# ALLPRINT-CAPBOARD-677512-GENERAL.net
KiCad netlist of a schematic drawn in Altium Designer
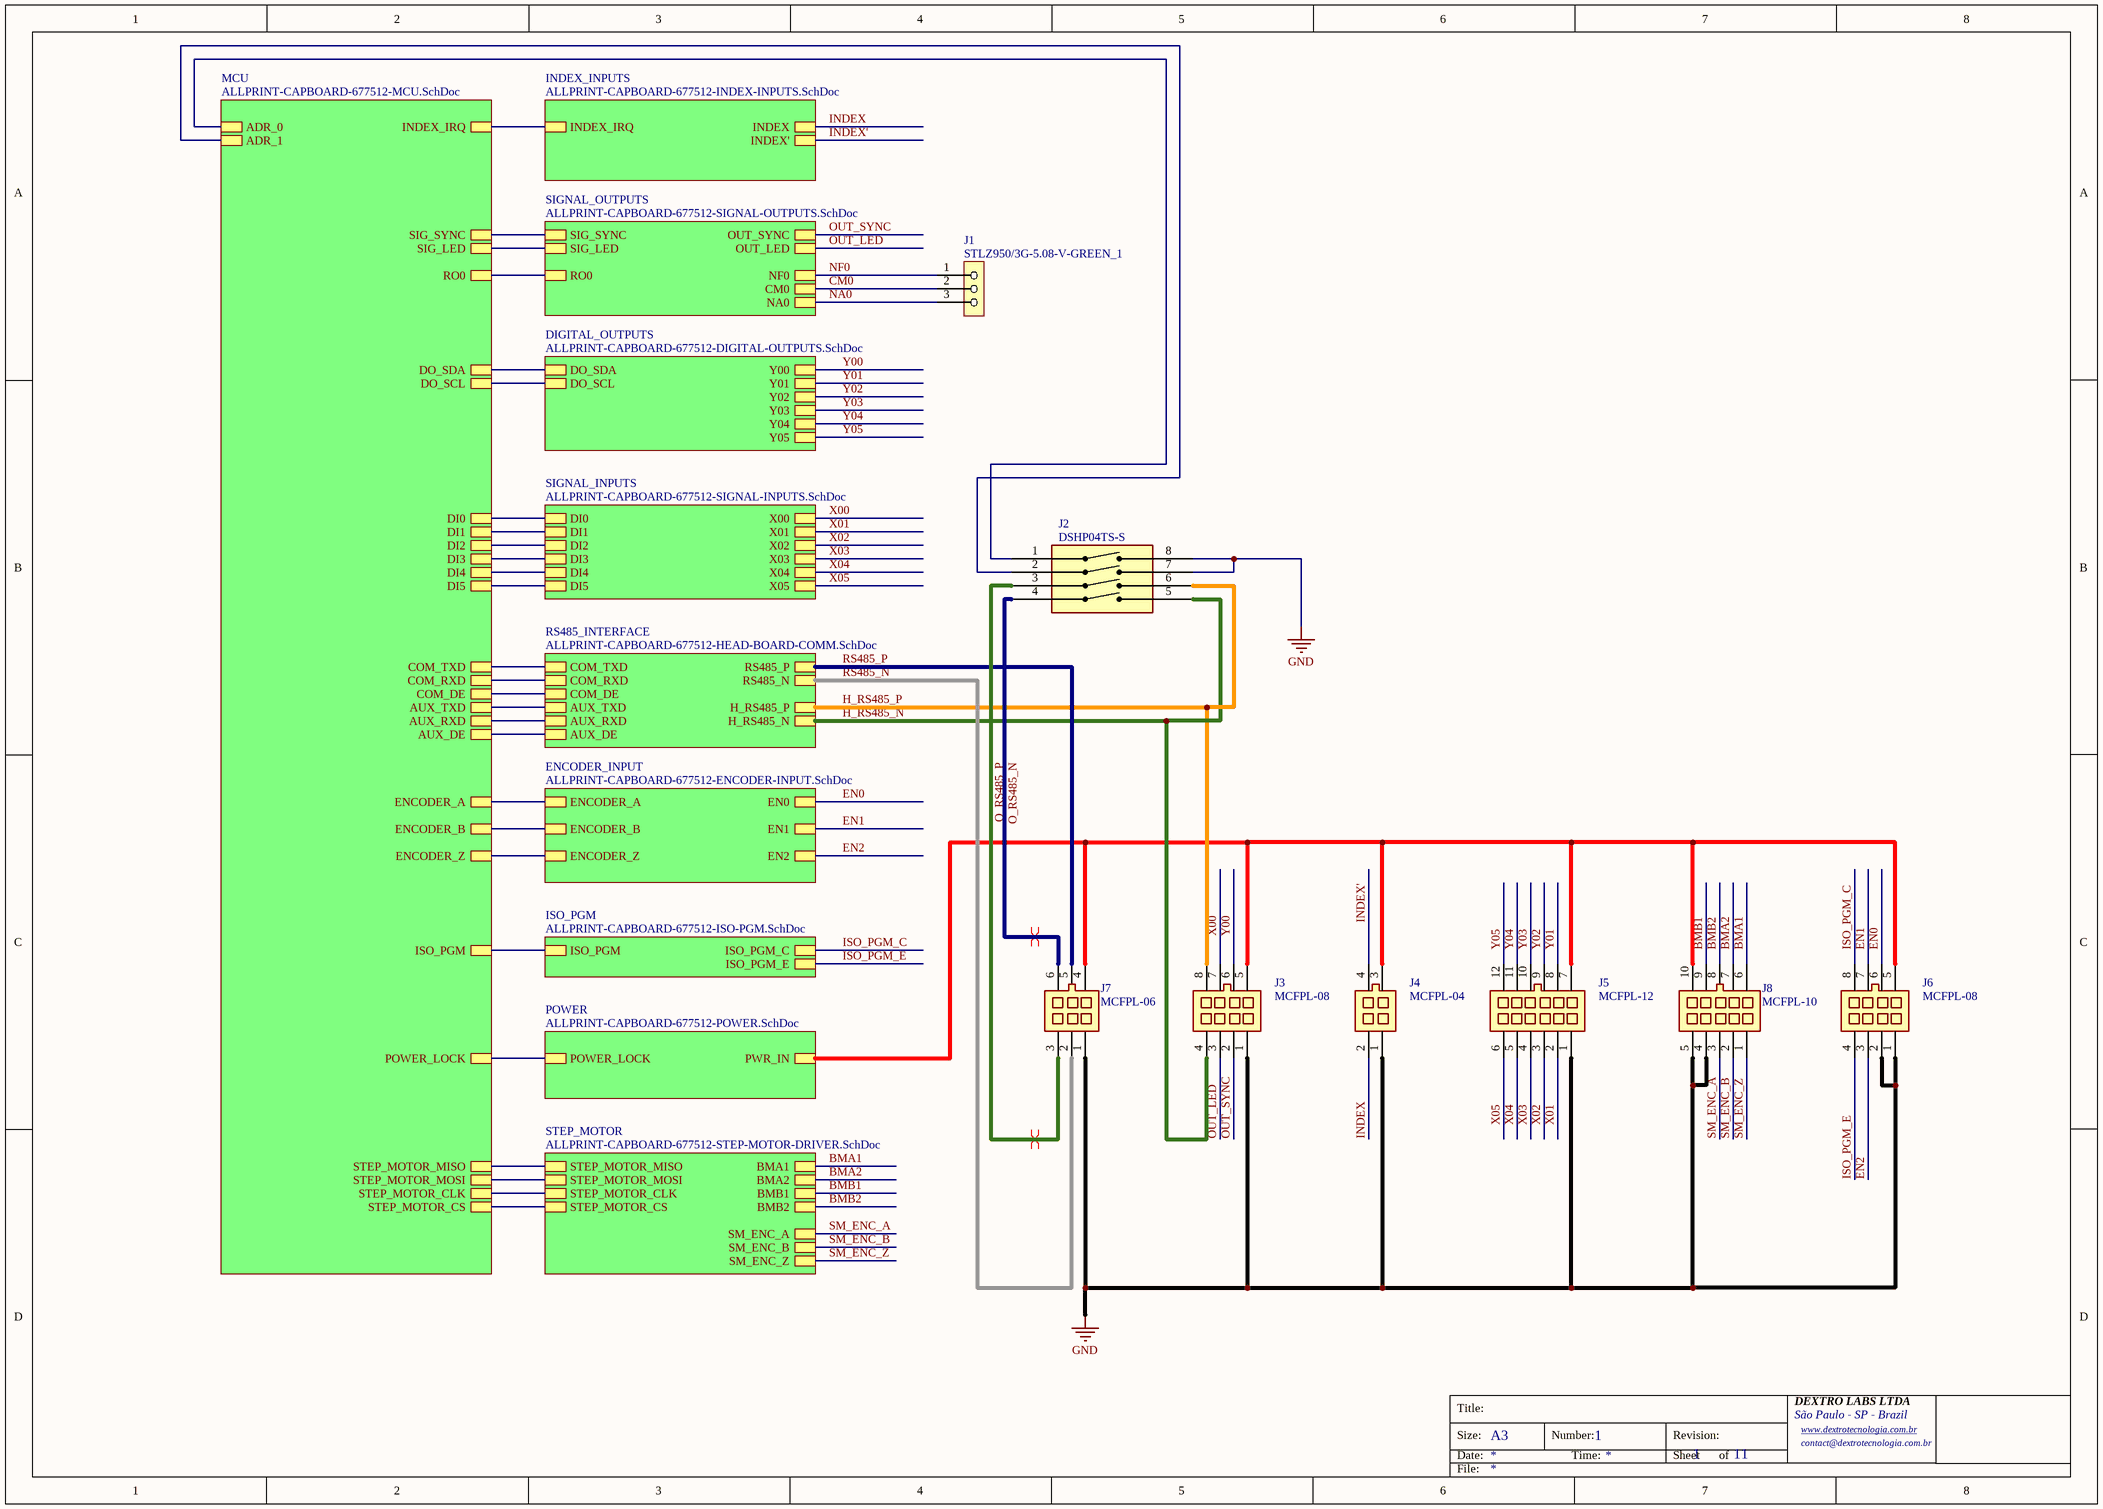
[diagram p0: ALLPRINT-CAPBOARD-677512-GENERAL.SchDoc]

(export (version "E")
  (design (tool "Eeschema 10.0.6"))
  (components
    (comp (ref "J1")
      (value "STLZ950/3G-5.08-V-GREEN_1")
      (footprint "STLZ950/3G-5.08-V")
      (description "CONECTOR PHOENIX MECANO 3 VIAS PASSO 5,08mm VERDE 180º")
      (libsource (lib "dextro-labs") (part "STLZ950/3G-5.08-V-GREEN"))
    )
    (comp (ref "J2")
      (value "DSHP04TS-S")
      (footprint "SW-SMD_8P-L6.7-W5.4-P1.27-LS8.5")
      (description "4 24V 25mA SPST 3,000 Cycles Black Slide, Recessed SMD-8P,6.7x5.4mm DIP Switches/SIP Switches ROHS")
      (libsource (lib "dextro-labs") (part "DSHP04TS-S"))
    )
    (comp (ref "J3")
      (value "MCFPL-08")
      (footprint "MCFPL-08")
      (description "CONECTOR-METALTEX-PASSO-3mm-90 GRAUS MONTAGEM PLACA-COMPATIVEL MICROFIT-8VIAS\r\n5A-250VCA")
      (libsource (lib "dextro-labs") (part "MCFPL-08"))
    )
    (comp (ref "J4")
      (value "MCFPL-04")
      (footprint "MCFPL-04")
      (description "CONECTOR-METALTEX-PASSO-3mm-90 GRAUS MONTAGEM PLACA-COMPATIVEL MICROFIT-4VIAS\r\n5A-250VCA")
      (libsource (lib "dextro-labs") (part "MCFPL-04"))
    )
    (comp (ref "J5")
      (value "MCFPL-12")
      (footprint "MCFPL-12")
      (description "CONECTOR-METALTEX-PASSO-3mm-90 GRAUS MONTAGEM PLACA-COMPATIVEL MICROFIT-12VIAS\r\n5A-250VCA")
      (libsource (lib "dextro-labs") (part "MCFPL-12"))
    )
    (comp (ref "J6")
      (value "MCFPL-08")
      (footprint "MCFPL-08")
      (description "CONECTOR-METALTEX-PASSO-3mm-90 GRAUS MONTAGEM PLACA-COMPATIVEL MICROFIT-8VIAS\r\n5A-250VCA")
      (libsource (lib "dextro-labs") (part "MCFPL-08"))
    )
    (comp (ref "J7")
      (value "MCFPL-06")
      (footprint "MCFPL-06")
      (description "CONECTOR-METALTEX-PASSO-3mm-90 GRAUS MONTAGEM PLACA-COMPATIVEL MICROFIT-6VIAS\r\n5A-250VCA")
      (libsource (lib "dextro-labs") (part "MCFPL-06"))
    )
    (comp (ref "J8")
      (value "MCFPL-10")
      (footprint "MCFPL-10")
      (description "CONECTOR-METALTEX-PASSO-3mm-90 GRAUS MONTAGEM PLACA-COMPATIVEL MICROFIT-10VIAS\r\n5A-250VCA")
      (libsource (lib "dextro-labs") (part "MCFPL-10"))
    )
  )
  (nets
    (net (code "1") (name "/ADR_0") (class "Default")
      (node (ref "J2") (pin "1") (pinfunction "1_1") (pintype "passive"))
    )
    (net (code "2") (name "/ADR_1") (class "Default")
      (node (ref "J2") (pin "2") (pinfunction "2_2") (pintype "passive"))
    )
    (net (code "6") (name "/BMA1") (class "Default")
      (node (ref "J8") (pin "6") (pinfunction "6_6") (pintype "passive"))
    )
    (net (code "7") (name "/BMA2") (class "Default")
      (node (ref "J8") (pin "7") (pinfunction "7_7") (pintype "passive"))
    )
    (net (code "8") (name "/BMB1") (class "Default")
      (node (ref "J8") (pin "9") (pinfunction "9_9") (pintype "passive"))
    )
    (net (code "9") (name "/BMB2") (class "Default")
      (node (ref "J8") (pin "8") (pinfunction "8_8") (pintype "passive"))
    )
    (net (code "10") (name "/CM0") (class "Default")
      (node (ref "J1") (pin "2") (pinfunction "2_2") (pintype "passive"))
    )
    (net (code "22") (name "/EN0") (class "Default")
      (node (ref "J6") (pin "6") (pinfunction "6_6") (pintype "passive"))
    )
    (net (code "23") (name "/EN1") (class "Default")
      (node (ref "J6") (pin "7") (pinfunction "7_7") (pintype "passive"))
    )
    (net (code "24") (name "/EN2") (class "Default")
      (node (ref "J6") (pin "3") (pinfunction "3_3") (pintype "passive"))
    )
    (net (code "28") (name "/H_RS485_N") (class "Default")
      (node (ref "J2") (pin "5") (pinfunction "5_5") (pintype "passive"))
      (node (ref "J3") (pin "4") (pinfunction "4_4") (pintype "passive"))
    )
    (net (code "29") (name "/H_RS485_P") (class "Default")
      (node (ref "J2") (pin "6") (pinfunction "6_6") (pintype "passive"))
      (node (ref "J3") (pin "8") (pinfunction "8_8") (pintype "passive"))
    )
    (net (code "30") (name "/INDEX") (class "Default")
      (node (ref "J4") (pin "2") (pinfunction "2_2") (pintype "passive"))
    )
    (net (code "31") (name "/INDEX'") (class "Default")
      (node (ref "J4") (pin "4") (pinfunction "4_4") (pintype "passive"))
    )
    (net (code "34") (name "/ISO_PGM_C") (class "Default")
      (node (ref "J6") (pin "8") (pinfunction "8_8") (pintype "passive"))
    )
    (net (code "35") (name "/ISO_PGM_E") (class "Default")
      (node (ref "J6") (pin "4") (pinfunction "4_4") (pintype "passive"))
    )
    (net (code "36") (name "/NA0") (class "Default")
      (node (ref "J1") (pin "3") (pinfunction "3_3") (pintype "passive"))
    )
    (net (code "37") (name "/NF0") (class "Default")
      (node (ref "J1") (pin "1") (pinfunction "1_1") (pintype "passive"))
    )
    (net (code "38") (name "/OUT_LED") (class "Default")
      (node (ref "J3") (pin "3") (pinfunction "3_3") (pintype "passive"))
    )
    (net (code "39") (name "/OUT_SYNC") (class "Default")
      (node (ref "J3") (pin "2") (pinfunction "2_2") (pintype "passive"))
    )
    (net (code "40") (name "/O_RS485_N") (class "Default")
      (node (ref "J2") (pin "4") (pinfunction "4_4") (pintype "passive"))
      (node (ref "J7") (pin "6") (pinfunction "6_6") (pintype "passive"))
    )
    (net (code "41") (name "/O_RS485_P") (class "Default")
      (node (ref "J2") (pin "3") (pinfunction "3_3") (pintype "passive"))
      (node (ref "J7") (pin "3") (pinfunction "3_3") (pintype "passive"))
    )
    (net (code "43") (name "/PWR_IN") (class "Default")
      (node (ref "J3") (pin "5") (pinfunction "5_5") (pintype "passive"))
      (node (ref "J4") (pin "3") (pinfunction "3_3") (pintype "passive"))
      (node (ref "J5") (pin "7") (pinfunction "7_7") (pintype "passive"))
      (node (ref "J6") (pin "5") (pinfunction "5_5") (pintype "passive"))
      (node (ref "J7") (pin "4") (pinfunction "4_4") (pintype "passive"))
      (node (ref "J8") (pin "10") (pinfunction "10_10") (pintype "passive"))
    )
    (net (code "45") (name "/RS485_N") (class "Default")
      (node (ref "J7") (pin "2") (pinfunction "2_2") (pintype "passive"))
    )
    (net (code "46") (name "/RS485_P") (class "Default")
      (node (ref "J7") (pin "5") (pinfunction "5_5") (pintype "passive"))
    )
    (net (code "49") (name "/SM_ENC_A") (class "Default")
      (node (ref "J8") (pin "3") (pinfunction "3_3") (pintype "passive"))
    )
    (net (code "50") (name "/SM_ENC_B") (class "Default")
      (node (ref "J8") (pin "2") (pinfunction "2_2") (pintype "passive"))
    )
    (net (code "51") (name "/SM_ENC_Z") (class "Default")
      (node (ref "J8") (pin "1") (pinfunction "1_1") (pintype "passive"))
    )
    (net (code "56") (name "/X00") (class "Default")
      (node (ref "J3") (pin "7") (pinfunction "7_7") (pintype "passive"))
    )
    (net (code "57") (name "/X01") (class "Default")
      (node (ref "J5") (pin "2") (pinfunction "2_2") (pintype "passive"))
    )
    (net (code "58") (name "/X02") (class "Default")
      (node (ref "J5") (pin "3") (pinfunction "3_3") (pintype "passive"))
    )
    (net (code "59") (name "/X03") (class "Default")
      (node (ref "J5") (pin "4") (pinfunction "4_4") (pintype "passive"))
    )
    (net (code "60") (name "/X04") (class "Default")
      (node (ref "J5") (pin "5") (pinfunction "5_5") (pintype "passive"))
    )
    (net (code "61") (name "/X05") (class "Default")
      (node (ref "J5") (pin "6") (pinfunction "6_6") (pintype "passive"))
    )
    (net (code "62") (name "/Y00") (class "Default")
      (node (ref "J3") (pin "6") (pinfunction "6_6") (pintype "passive"))
    )
    (net (code "63") (name "/Y01") (class "Default")
      (node (ref "J5") (pin "8") (pinfunction "8_8") (pintype "passive"))
    )
    (net (code "64") (name "/Y02") (class "Default")
      (node (ref "J5") (pin "9") (pinfunction "9_9") (pintype "passive"))
    )
    (net (code "65") (name "/Y03") (class "Default")
      (node (ref "J5") (pin "10") (pinfunction "10_10") (pintype "passive"))
    )
    (net (code "66") (name "/Y04") (class "Default")
      (node (ref "J5") (pin "11") (pinfunction "11_11") (pintype "passive"))
    )
    (net (code "67") (name "/Y05") (class "Default")
      (node (ref "J5") (pin "12") (pinfunction "12_12") (pintype "passive"))
    )
    (net (code "68") (name "GND") (class "Default")
      (node (ref "J2") (pin "7") (pinfunction "7_7") (pintype "passive"))
      (node (ref "J2") (pin "8") (pinfunction "8_8") (pintype "passive"))
      (node (ref "J3") (pin "1") (pinfunction "1_1") (pintype "passive"))
      (node (ref "J4") (pin "1") (pinfunction "1_1") (pintype "passive"))
      (node (ref "J5") (pin "1") (pinfunction "1_1") (pintype "passive"))
      (node (ref "J6") (pin "1") (pinfunction "1_1") (pintype "passive"))
      (node (ref "J6") (pin "2") (pinfunction "2_2") (pintype "passive"))
      (node (ref "J7") (pin "1") (pinfunction "1_1") (pintype "passive"))
      (node (ref "J8") (pin "4") (pinfunction "4_4") (pintype "passive"))
      (node (ref "J8") (pin "5") (pinfunction "5_5") (pintype "passive"))
    )
  )
)
